# power3v3.net
KiCad netlist of a schematic drawn in Altium Designer
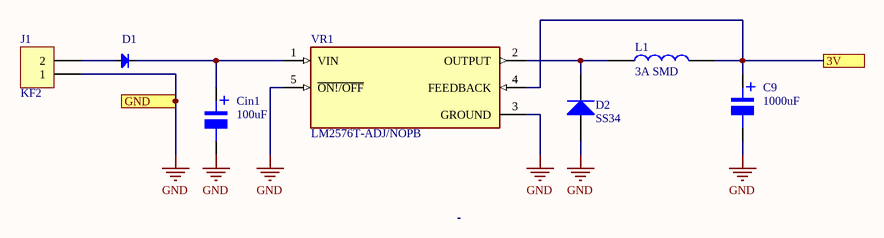
[diagram p0: power3v3.SchDoc]

(export (version "E")
  (design (tool "Eeschema 10.0.6"))
  (components
    (comp (ref "C9")
      (value "1000uF")
      (footprint "tu nhom 10 (G)")
      (description "Dán")
      (libsource (lib "Altium_Lib_by_KhueNguyenCreator") (part "Tu Nhom 1000uF 10V"))
    )
    (comp (ref "Cin1")
      (value "100uF")
      (footprint "tu nhom 6.3 (d)")
      (description "Dán")
      (libsource (lib "Altium_Lib_by_KhueNguyenCreator") (part "Tu Nhom 100uF 16V"))
    )
    (comp (ref "D1")
      (value "Diode")
      (footprint "DIO-3A")
      (description "Default Diode")
      (fields (field (name "PUBLISHER") "Altium Limited"))
      (libsource (lib "LIBRARY1") (part "Diode"))
    )
    (comp (ref "D2")
      (value "SS34")
      (footprint "DIODE SMA")
      (description "Dán")
      (libsource (lib "Altium_Lib_by_KhueNguyenCreator") (part "Diode SS34 ( 1N5822 )"))
    )
    (comp (ref "J1")
      (value "KF2")
      (footprint "KF2-3.5")
      (fields
        (field (name "MANUFACTURER") "Würth Elektronik eiSos GmbH")
        (field (name "PARTNO") "691103110002")
        (field (name "CREATED BY") "Karrer Zheng")
      )
      (libsource (lib "LIBRARY1") (part "KF2"))
    )
    (comp (ref "L1")
      (value "3A SMD")
      (footprint "Cuon Cam 12x12x10")
      (description "Dán")
      (libsource (lib "Altium_Lib_by_KhueNguyenCreator") (part "CUON CAM 100uH SMD"))
    )
    (comp (ref "VR1")
      (value "LM2576T-ADJ/NOPB")
      (footprint "TO170P1067X483X1651-5")
      (description "SIMPLE SWITCHERÂ® 40V, 3A Low Component Count Step-Down Regulator")
      (libsource (lib "LinhKienDoAn") (part "LM2576T-ADJ/NOPB"))
    )
  )
  (nets
    (net (code "1") (name "/3V") (class "Default")
      (node (ref "C9") (pin "1") (pinfunction "1_1") (pintype "passive"))
      (node (ref "L1") (pin "2") (pinfunction "2_2") (pintype "passive"))
      (node (ref "VR1") (pin "4") (pinfunction "FEEDBACK_4") (pintype "input"))
    )
    (net (code "2") (name "GND") (class "Default")
      (node (ref "C9") (pin "2") (pinfunction "2_2") (pintype "passive"))
      (node (ref "Cin1") (pin "2") (pinfunction "2_2") (pintype "passive"))
      (node (ref "D2") (pin "1") (pinfunction "A_1") (pintype "passive"))
      (node (ref "J1") (pin "1") (pinfunction "1_1") (pintype "passive"))
      (node (ref "VR1") (pin "3") (pinfunction "GROUND_3") (pintype "power_in"))
      (node (ref "VR1") (pin "5") (pinfunction "~{ON!/OFF}_5") (pintype "input"))
    )
    (net (code "3") (name "Net-(D1-A)") (class "Default")
      (node (ref "D1") (pin "1") (pinfunction "A_1") (pintype "passive"))
      (node (ref "J1") (pin "2") (pinfunction "2_2") (pintype "passive"))
    )
    (net (code "4") (name "Net-(D1-K)") (class "Default")
      (node (ref "Cin1") (pin "1") (pinfunction "1_1") (pintype "passive"))
      (node (ref "D1") (pin "2") (pinfunction "K_2") (pintype "passive"))
      (node (ref "VR1") (pin "1") (pinfunction "VIN_1") (pintype "input"))
    )
    (net (code "5") (name "Net-(D2-K)") (class "Default")
      (node (ref "D2") (pin "2") (pinfunction "K_2") (pintype "passive"))
      (node (ref "L1") (pin "1") (pinfunction "1_1") (pintype "passive"))
      (node (ref "VR1") (pin "2") (pinfunction "OUTPUT_2") (pintype "output"))
    )
  )
)
